# imu_finger.net
KiCad netlist of a schematic drawn in EAGLE
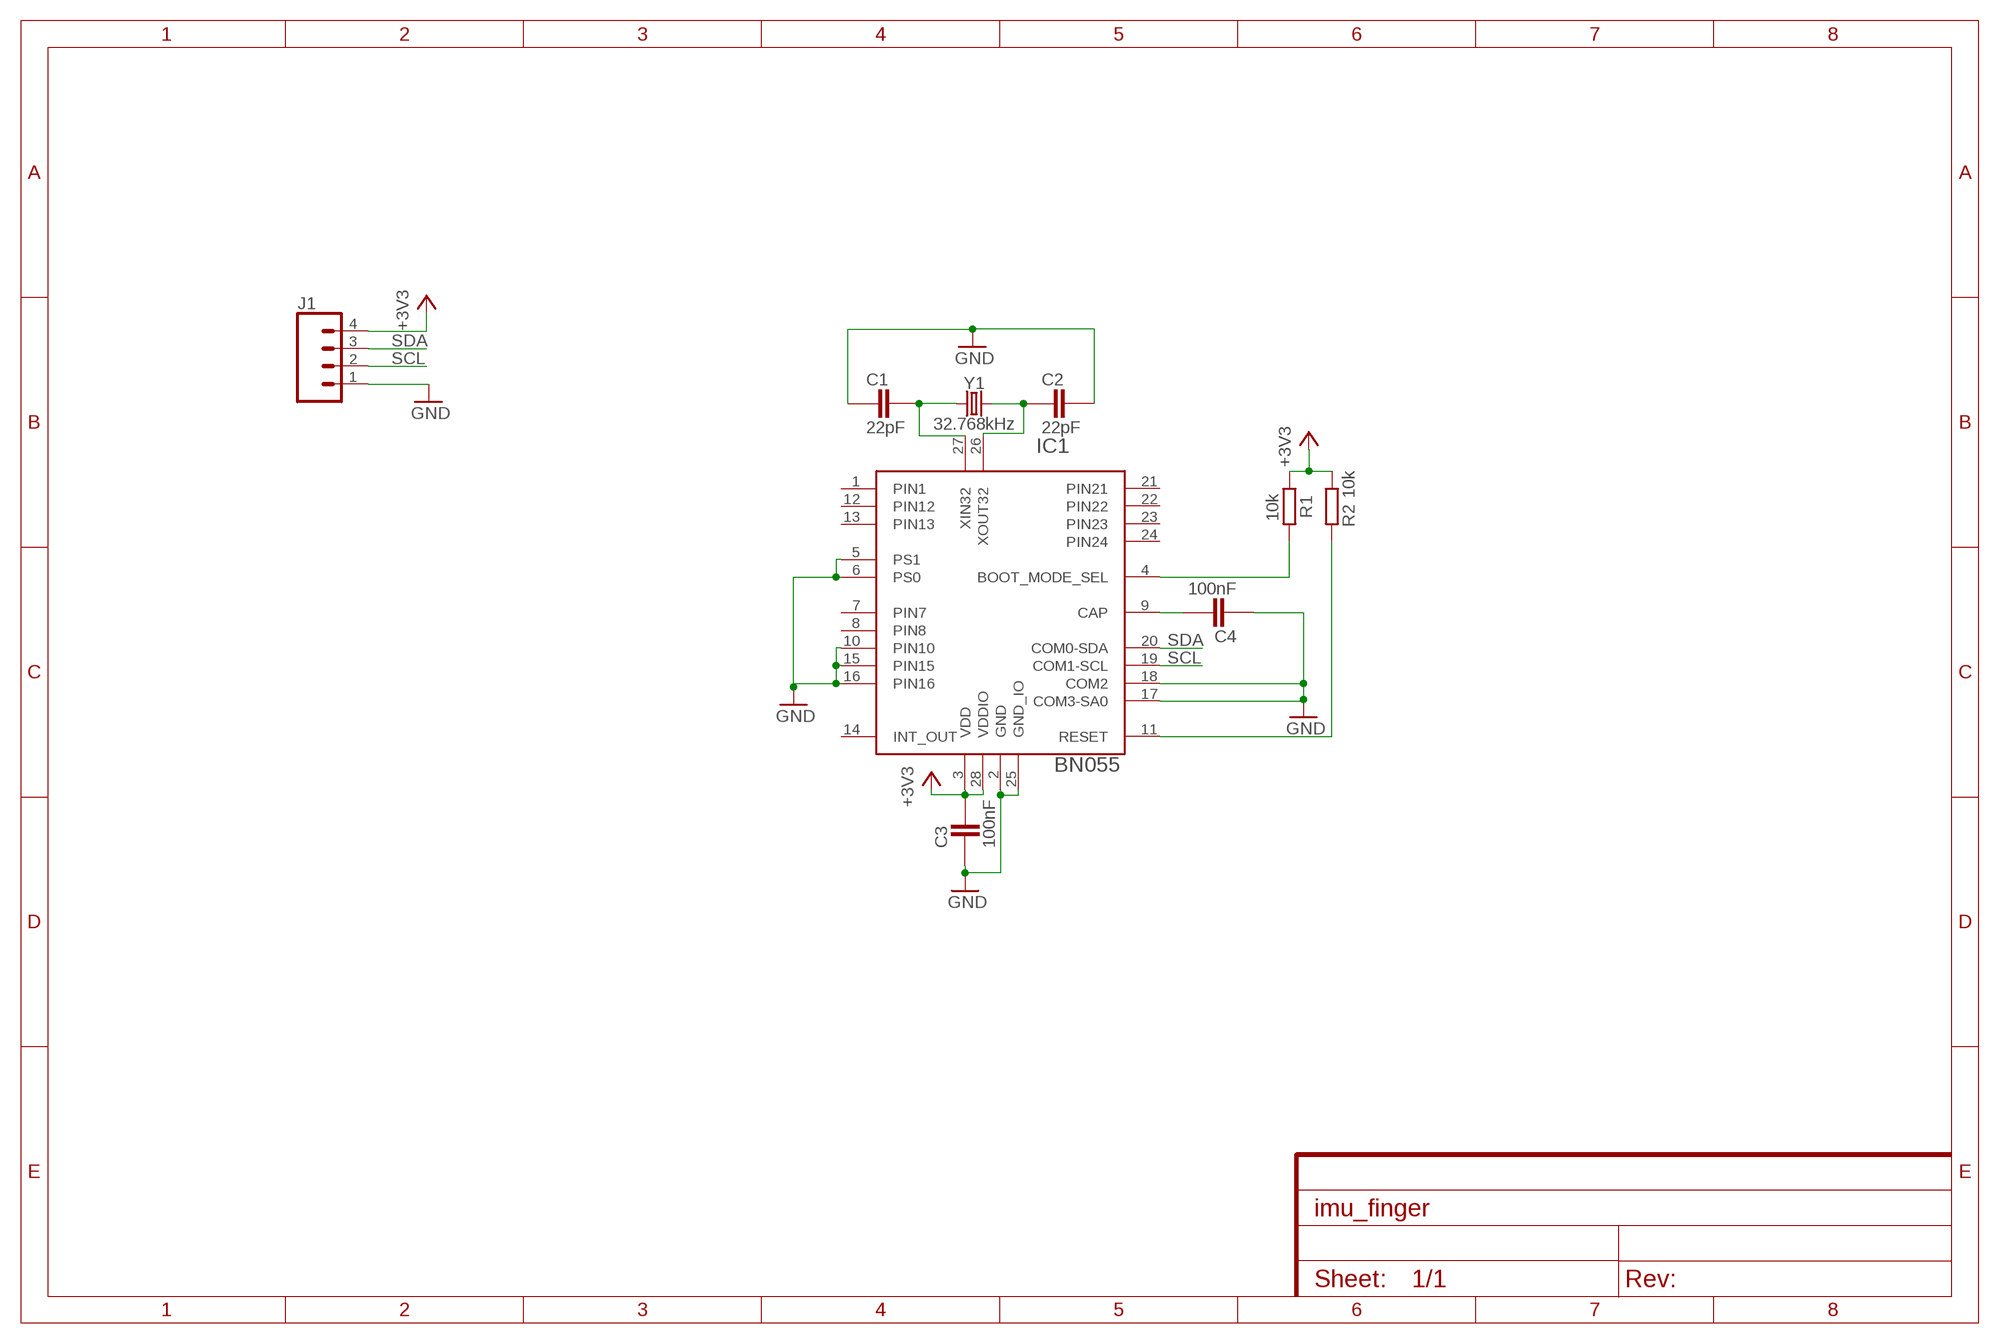
[diagram p0: schematic, sheet 1]

(export (version "E")
  (design (tool "Eeschema 10.0.6"))
  (components
    (comp (ref "C1")
      (value "22pF")
      (footprint "eagle-import:CAPC1608X92N")
      (libsource (lib "eagle-import") (part "CAPACITOR_0603"))
    )
    (comp (ref "C2")
      (value "22pF")
      (footprint "eagle-import:CAPC1608X92N")
      (libsource (lib "eagle-import") (part "CAPACITOR_0603"))
    )
    (comp (ref "C3")
      (value "100nF")
      (footprint "eagle-import:CAPC1608X92N")
      (libsource (lib "eagle-import") (part "CAPACITOR_0603"))
    )
    (comp (ref "C4")
      (value "100nF")
      (footprint "eagle-import:CAPC1608X92N")
      (libsource (lib "eagle-import") (part "CAPACITOR_0603"))
    )
    (comp (ref "IC1")
      (value "BN055")
      (footprint "eagle-import:LGA-28_3.80X5.20_0.5")
      (fields (field (name "PART_NUMBER") "BNO055"))
      (libsource (lib "eagle-import") (part "1658_BNO055"))
    )
    (comp (ref "J1")
      (value "CONN_04SMD2")
      (footprint "eagle-import:1X04_1MM_RA")
      (libsource (lib "eagle-import") (part "CONN_04SMD2"))
    )
    (comp (ref "R1")
      (value "10k")
      (footprint "eagle-import:RESC1608X55N")
      (libsource (lib "eagle-import") (part "RESISTOR_0603"))
    )
    (comp (ref "R2")
      (value "10k")
      (footprint "eagle-import:RESC1608X55N")
      (libsource (lib "eagle-import") (part "RESISTOR_0603"))
    )
    (comp (ref "Y1")
      (value "32.768kHz")
      (footprint "eagle-import:CRYSTAL-SMD-3.2X1.5MM")
      (libsource (lib "eagle-import") (part "CRYSTAL-32.768KHZSMD-3.2X1.5"))
    )
  )
  (nets
    (net (code "1") (name "+3V3") (class "Default")
      (node (ref "C3") (pin "2") (pinfunction "2_2") (pintype "passive"))
      (node (ref "IC1") (pin "28") (pinfunction "VDDIO_28") (pintype "power_in"))
      (node (ref "IC1") (pin "3") (pinfunction "VDD_3") (pintype "power_in"))
      (node (ref "J1") (pin "4") (pinfunction "4_4") (pintype "passive"))
      (node (ref "R1") (pin "1") (pinfunction "1_1") (pintype "passive"))
      (node (ref "R2") (pin "1") (pinfunction "1_1") (pintype "passive"))
    )
    (net (code "2") (name "/SCL") (class "Default")
      (node (ref "IC1") (pin "19") (pinfunction "COM1-SCL_19") (pintype "bidirectional"))
      (node (ref "J1") (pin "2") (pinfunction "2_2") (pintype "passive"))
    )
    (net (code "3") (name "/SDA") (class "Default")
      (node (ref "IC1") (pin "20") (pinfunction "COM0-SDA_20") (pintype "bidirectional"))
      (node (ref "J1") (pin "3") (pinfunction "3_3") (pintype "passive"))
    )
    (net (code "4") (name "GND") (class "Default")
      (node (ref "C1") (pin "1") (pinfunction "1_1") (pintype "passive"))
      (node (ref "C2") (pin "2") (pinfunction "2_2") (pintype "passive"))
      (node (ref "C3") (pin "1") (pinfunction "1_1") (pintype "passive"))
      (node (ref "C4") (pin "1") (pinfunction "1_1") (pintype "passive"))
      (node (ref "IC1") (pin "10") (pinfunction "PIN10_10") (pintype "passive"))
      (node (ref "IC1") (pin "15") (pinfunction "PIN15_15") (pintype "passive"))
      (node (ref "IC1") (pin "16") (pinfunction "PIN16_16") (pintype "passive"))
      (node (ref "IC1") (pin "17") (pinfunction "COM3-SA0_17") (pintype "bidirectional"))
      (node (ref "IC1") (pin "18") (pinfunction "COM2_18") (pintype "bidirectional"))
      (node (ref "IC1") (pin "2") (pinfunction "GND_2") (pintype "power_in"))
      (node (ref "IC1") (pin "25") (pinfunction "GND_IO_25") (pintype "power_in"))
      (node (ref "IC1") (pin "5") (pinfunction "PS1_5") (pintype "input"))
      (node (ref "IC1") (pin "6") (pinfunction "PS0_6") (pintype "input"))
      (node (ref "J1") (pin "1") (pinfunction "1_1") (pintype "passive"))
    )
    (net (code "5") (name "Net-(IC1-BOOT_MODE_SEL)") (class "Default")
      (node (ref "IC1") (pin "4") (pinfunction "BOOT_MODE_SEL_4") (pintype "input"))
      (node (ref "R1") (pin "2") (pinfunction "2_2") (pintype "passive"))
    )
    (net (code "6") (name "Net-(IC1-CAP)") (class "Default")
      (node (ref "C4") (pin "2") (pinfunction "2_2") (pintype "passive"))
      (node (ref "IC1") (pin "9") (pinfunction "CAP_9") (pintype "tri_state"))
    )
    (net (code "7") (name "Net-(IC1-RESET)") (class "Default")
      (node (ref "IC1") (pin "11") (pinfunction "RESET_11") (pintype "input"))
      (node (ref "R2") (pin "2") (pinfunction "2_2") (pintype "passive"))
    )
    (net (code "8") (name "Net-(IC1-XIN32)") (class "Default")
      (node (ref "C1") (pin "2") (pinfunction "2_2") (pintype "passive"))
      (node (ref "IC1") (pin "27") (pinfunction "XIN32_27") (pintype "bidirectional"))
      (node (ref "Y1") (pin "P$1") (pinfunction "1_P$1") (pintype "passive"))
    )
    (net (code "9") (name "Net-(IC1-XOUT32)") (class "Default")
      (node (ref "C2") (pin "1") (pinfunction "1_1") (pintype "passive"))
      (node (ref "IC1") (pin "26") (pinfunction "XOUT32_26") (pintype "output"))
      (node (ref "Y1") (pin "P$2") (pinfunction "2_P$2") (pintype "passive"))
    )
    (net (code "10") (name "unconnected-(IC1-INT_OUT-Pad14)") (class "Default")
      (node (ref "IC1") (pin "14") (pinfunction "INT_OUT_14") (pintype "output"))
    )
    (net (code "11") (name "unconnected-(IC1-PIN1-Pad1)") (class "Default")
      (node (ref "IC1") (pin "1") (pinfunction "PIN1_1") (pintype "no_connect"))
    )
    (net (code "12") (name "unconnected-(IC1-PIN7-Pad7)") (class "Default")
      (node (ref "IC1") (pin "7") (pinfunction "PIN7_7") (pintype "tri_state"))
    )
    (net (code "13") (name "unconnected-(IC1-PIN8-Pad8)") (class "Default")
      (node (ref "IC1") (pin "8") (pinfunction "PIN8_8") (pintype "tri_state"))
    )
    (net (code "14") (name "unconnected-(IC1-PIN12-Pad12)") (class "Default")
      (node (ref "IC1") (pin "12") (pinfunction "PIN12_12") (pintype "passive"))
    )
    (net (code "15") (name "unconnected-(IC1-PIN13-Pad13)") (class "Default")
      (node (ref "IC1") (pin "13") (pinfunction "PIN13_13") (pintype "passive"))
    )
    (net (code "16") (name "unconnected-(IC1-PIN21-Pad21)") (class "Default")
      (node (ref "IC1") (pin "21") (pinfunction "PIN21_21") (pintype "passive"))
    )
    (net (code "17") (name "unconnected-(IC1-PIN22-Pad22)") (class "Default")
      (node (ref "IC1") (pin "22") (pinfunction "PIN22_22") (pintype "passive"))
    )
    (net (code "18") (name "unconnected-(IC1-PIN23-Pad23)") (class "Default")
      (node (ref "IC1") (pin "23") (pinfunction "PIN23_23") (pintype "passive"))
    )
    (net (code "19") (name "unconnected-(IC1-PIN24-Pad24)") (class "Default")
      (node (ref "IC1") (pin "24") (pinfunction "PIN24_24") (pintype "passive"))
    )
  )
)
